# Power.net
KiCad netlist of a schematic drawn in Altium Designer
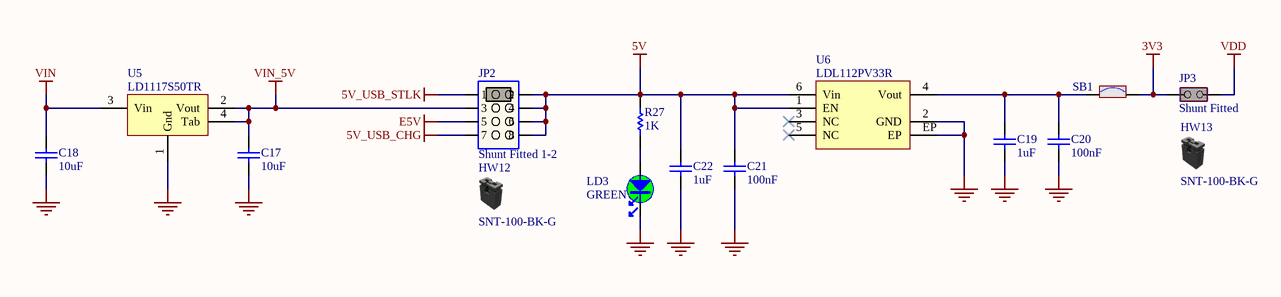
[diagram p0: Power.SchDoc]

(export (version "E")
  (design (tool "Eeschema 10.0.6"))
  (components
    (comp (ref "C17")
      (value "10uF")
      (footprint "C0805")
      (description "Capacitor, MLCC, 10uF, 25V, X5R, 10%, 0805, T=0,85mm")
      (fields
        (field (name "INTERNAL_PART_NUMBER") "MCD-00014")
        (field (name "MANUFACTURER_PART_NUMBER") "CC0805KRX5R8BB106")
        (field (name "PROVIDED_BY") "SUBCO")
      )
      (libsource (lib "MCD_PARTS_database") (part "Capacitor"))
    )
    (comp (ref "C18")
      (value "10uF")
      (footprint "C0805")
      (description "Capacitor, MLCC, 10uF, 25V, X5R, 10%, 0805, T=0,85mm")
      (fields
        (field (name "INTERNAL_PART_NUMBER") "MCD-00014")
        (field (name "MANUFACTURER_PART_NUMBER") "CC0805KRX5R8BB106")
        (field (name "PROVIDED_BY") "SUBCO")
      )
      (libsource (lib "MCD_PARTS_database") (part "Capacitor"))
    )
    (comp (ref "C19")
      (value "1uF")
      (footprint "C0603")
      (description "Capacitor, MLCC, 1uF, 16V, X5R, 10%, 0603, T=0,8mm")
      (fields
        (field (name "INTERNAL_PART_NUMBER") "MCD-00010")
        (field (name "MANUFACTURER_PART_NUMBER") "CC0603KRX5R7BB105")
        (field (name "PROVIDED_BY") "SUBCO")
      )
      (libsource (lib "MCD_PARTS_database") (part "Capacitor"))
    )
    (comp (ref "C20")
      (value "100nF")
      (footprint "C0603")
      (description "Capacitor, MLCC, 100nF, 16V, X7R, 10%, 0603, T=0,8mm")
      (fields
        (field (name "INTERNAL_PART_NUMBER") "MCD-00211")
        (field (name "MANUFACTURER_PART_NUMBER") "CC0603KRX7R7BB104")
        (field (name "PROVIDED_BY") "SUBCO")
      )
      (libsource (lib "MCD_PARTS_database") (part "Capacitor"))
    )
    (comp (ref "C21")
      (value "100nF")
      (footprint "C0603")
      (description "Capacitor, MLCC, 100nF, 16V, X7R, 10%, 0603, T=0,8mm")
      (fields
        (field (name "INTERNAL_PART_NUMBER") "MCD-00211")
        (field (name "MANUFACTURER_PART_NUMBER") "CC0603KRX7R7BB104")
        (field (name "PROVIDED_BY") "SUBCO")
      )
      (libsource (lib "MCD_PARTS_database") (part "Capacitor"))
    )
    (comp (ref "C22")
      (value "1uF")
      (footprint "C0603")
      (description "Capacitor, MLCC, 1uF, 16V, X5R, 10%, 0603, T=0,8mm")
      (fields
        (field (name "INTERNAL_PART_NUMBER") "MCD-00010")
        (field (name "MANUFACTURER_PART_NUMBER") "CC0603KRX5R7BB105")
        (field (name "PROVIDED_BY") "SUBCO")
      )
      (libsource (lib "MCD_PARTS_database") (part "Capacitor"))
    )
    (comp (ref "HW12")
      (value "SNT-100-BK-G")
      (description "SHUNT 2.54mm BLACK")
      (fields
        (field (name "INTERNAL_PART_NUMBER") "MCD-00043")
        (field (name "MANUFACTURER") "SAMTEC")
        (field (name "PROVIDED_BY") "SUBCO")
      )
      (libsource (lib "MCD_PARTS_database") (part "Shunt Black 2.54mm"))
    )
    (comp (ref "HW13")
      (value "SNT-100-BK-G")
      (description "SHUNT 2.54mm BLACK")
      (fields
        (field (name "INTERNAL_PART_NUMBER") "MCD-00043")
        (field (name "MANUFACTURER") "SAMTEC")
        (field (name "PROVIDED_BY") "SUBCO")
      )
      (libsource (lib "MCD_PARTS_database") (part "Shunt Black 2.54mm"))
    )
    (comp (ref "JP2")
      (value "Shunt Fitted 1-2")
      (footprint "CON_SAMTEC_TSW-104-07-X-D")
      (description "Header, 4x2, 2,54mm, VR, TH, Height 5.84mm/2.54mm - Shunt Fitted 1-2")
      (fields
        (field (name "INTERNAL_PART_NUMBER") "MCD-00686")
        (field (name "MANUFACTURER_PART_NUMBER") "TSW-104-07-x-D")
        (field (name "PROVIDED_BY") "SUBCO")
      )
      (libsource (lib "MCD_PARTS_database") (part "Jumper_Header 4x2 Fitted 1-2"))
    )
    (comp (ref "JP3")
      (value "Shunt Fitted")
      (footprint "CON_SAMTEC_TSW-102-07-G-S")
      (description "Header, 2x1, 2,54mm, VR, TH, Height 5.84mm/2.54mm - Shunt Fitted by default")
      (fields
        (field (name "INTERNAL_PART_NUMBER") "MCD-00683")
        (field (name "MANUFACTURER_PART_NUMBER") "TSW-102-07-x-S")
        (field (name "PROVIDED_BY") "SUBCO")
      )
      (libsource (lib "MCD_PARTS_database") (part "Jumper_Header 2x1 Fitted"))
    )
    (comp (ref "LD3")
      (value "GREEN")
      (footprint "LED_0603_GREEN")
      (description "LED, Green, 0603")
      (fields
        (field (name "INTERNAL_PART_NUMBER") "MCD-00050")
        (field (name "MANUFACTURER_PART_NUMBER") "19-213SYGC/S530-E2/TR8")
        (field (name "PROVIDED_BY") "SUBCO")
      )
      (libsource (lib "MCD_PARTS_database") (part "LED_green"))
    )
    (comp (ref "R27")
      (value "1K")
      (footprint "R0603")
      (description "Resistor,1K,0603,1%,1/10W")
      (fields
        (field (name "INTERNAL_PART_NUMBER") "MCD-00070")
        (field (name "MANUFACTURER_PART_NUMBER") "RC0603FR-071KL")
        (field (name "PROVIDED_BY") "SUBCO")
      )
      (libsource (lib "MCD_PARTS_database") (part "Resistor"))
    )
    (comp (ref "SB1")
      (value "SB_ON")
      (footprint "SOLDER-BRIDGE_R0603-0R")
      (description "Solder Bridge ON")
      (fields
        (field (name "INTERNAL_PART_NUMBER") "MCD-00071")
        (field (name "MANUFACTURER_PART_NUMBER") "RC0603JR-070RL")
        (field (name "PROVIDED_BY") "SUBCO")
      )
      (libsource (lib "MCD_PARTS_database") (part "SB_ON"))
    )
    (comp (ref "U5")
      (value "LD1117S50TR")
      (footprint "REG_SOT223-TAB")
      (description "IC REG LDO 5V 0.8A SOT223")
      (fields
        (field (name "INTERNAL_PART_NUMBER") "MCD-00088")
        (field (name "MANUFACTURER") "STMICROELECTRONICS")
        (field (name "PROVIDED_BY") "SUBCO with ST control")
      )
      (libsource (lib "MCD_PARTS_database") (part "LD1117S50TR"))
    )
    (comp (ref "U6")
      (value "LDL112PV33R")
      (footprint "ICC_DFN6-EPAD_3X3_P095")
      (description "1.2 A low quiescent current LDO with reverse current protection")
      (fields
        (field (name "INTERNAL_PART_NUMBER") "MCD-00664")
        (field (name "MANUFACTURER") "STMICROELECTRONICS")
        (field (name "PROVIDED_BY") "SUBCO with ST control")
      )
      (libsource (lib "MCD_PARTS_database") (part "LDL112PV33R"))
    )
  )
  (nets
    (net (code "1") (name "3V3") (class "Default")
      (node (ref "JP3") (pin "2") (pinfunction "NO_2") (pintype "passive"))
      (node (ref "SB1") (pin "2") (pinfunction "2_2") (pintype "passive"))
    )
    (net (code "2") (name "5V") (class "Default")
      (node (ref "C21") (pin "2") (pinfunction "2_2") (pintype "passive"))
      (node (ref "C22") (pin "2") (pinfunction "2_2") (pintype "passive"))
      (node (ref "JP2") (pin "2") (pinfunction "2_2") (pintype "passive"))
      (node (ref "JP2") (pin "4") (pinfunction "4_4") (pintype "passive"))
      (node (ref "JP2") (pin "6") (pinfunction "6_6") (pintype "passive"))
      (node (ref "JP2") (pin "8") (pinfunction "8_8") (pintype "passive"))
      (node (ref "R27") (pin "1") (pinfunction "1_1") (pintype "passive"))
      (node (ref "U6") (pin "1") (pinfunction "EN_1") (pintype "passive"))
      (node (ref "U6") (pin "6") (pinfunction "Vin_6") (pintype "passive"))
    )
    (net (code "3") (name "5V_USB_CHG") (class "Default")
      (node (ref "JP2") (pin "7") (pinfunction "7_7") (pintype "passive"))
    )
    (net (code "4") (name "5V_USB_STLK") (class "Default")
      (node (ref "JP2") (pin "1") (pinfunction "1_1") (pintype "passive"))
    )
    (net (code "5") (name "E5V") (class "Default")
      (node (ref "JP2") (pin "5") (pinfunction "5_5") (pintype "passive"))
    )
    (net (code "6") (name "GND") (class "Default")
      (node (ref "C17") (pin "1") (pinfunction "1_1") (pintype "passive"))
      (node (ref "C18") (pin "1") (pinfunction "1_1") (pintype "passive"))
      (node (ref "C19") (pin "1") (pinfunction "1_1") (pintype "passive"))
      (node (ref "C20") (pin "1") (pinfunction "1_1") (pintype "passive"))
      (node (ref "C21") (pin "1") (pinfunction "1_1") (pintype "passive"))
      (node (ref "C22") (pin "1") (pinfunction "1_1") (pintype "passive"))
      (node (ref "LD3") (pin "2") (pintype "passive"))
      (node (ref "U5") (pin "1") (pinfunction "Gnd_1") (pintype "passive"))
      (node (ref "U6") (pin "2") (pinfunction "GND_2") (pintype "passive"))
      (node (ref "U6") (pin "EP") (pinfunction "EP_EP") (pintype "passive"))
    )
    (net (code "7") (name "Net-(LD3-Pad1)") (class "Default")
      (node (ref "LD3") (pin "1") (pintype "passive"))
      (node (ref "R27") (pin "2") (pinfunction "2_2") (pintype "passive"))
    )
    (net (code "8") (name "Net-(U6-Vout)") (class "Default")
      (node (ref "C19") (pin "2") (pinfunction "2_2") (pintype "passive"))
      (node (ref "C20") (pin "2") (pinfunction "2_2") (pintype "passive"))
      (node (ref "SB1") (pin "1") (pinfunction "1_1") (pintype "passive"))
      (node (ref "U6") (pin "4") (pinfunction "Vout_4") (pintype "passive"))
    )
    (net (code "9") (name "VDD") (class "Default")
      (node (ref "JP3") (pin "1") (pinfunction "COMMON_1") (pintype "passive"))
    )
    (net (code "10") (name "VIN") (class "Default")
      (node (ref "C18") (pin "2") (pinfunction "2_2") (pintype "passive"))
      (node (ref "U5") (pin "3") (pinfunction "Vin_3") (pintype "passive"))
    )
    (net (code "11") (name "VIN_5V") (class "Default")
      (node (ref "C17") (pin "2") (pinfunction "2_2") (pintype "passive"))
      (node (ref "JP2") (pin "3") (pinfunction "3_3") (pintype "passive"))
      (node (ref "U5") (pin "2") (pinfunction "Vout_2") (pintype "passive"))
      (node (ref "U5") (pin "4") (pinfunction "Tab_4") (pintype "passive"))
    )
    (net (code "12") (name "unconnected-(U6-NC-Pad3)") (class "Default")
      (node (ref "U6") (pin "3") (pinfunction "NC_3") (pintype "passive+no_connect"))
    )
    (net (code "13") (name "unconnected-(U6-NC-Pad5)") (class "Default")
      (node (ref "U6") (pin "5") (pinfunction "NC_5") (pintype "passive+no_connect"))
    )
  )
)
